# TPS5450.net
KiCad netlist of a schematic drawn in Altium Designer
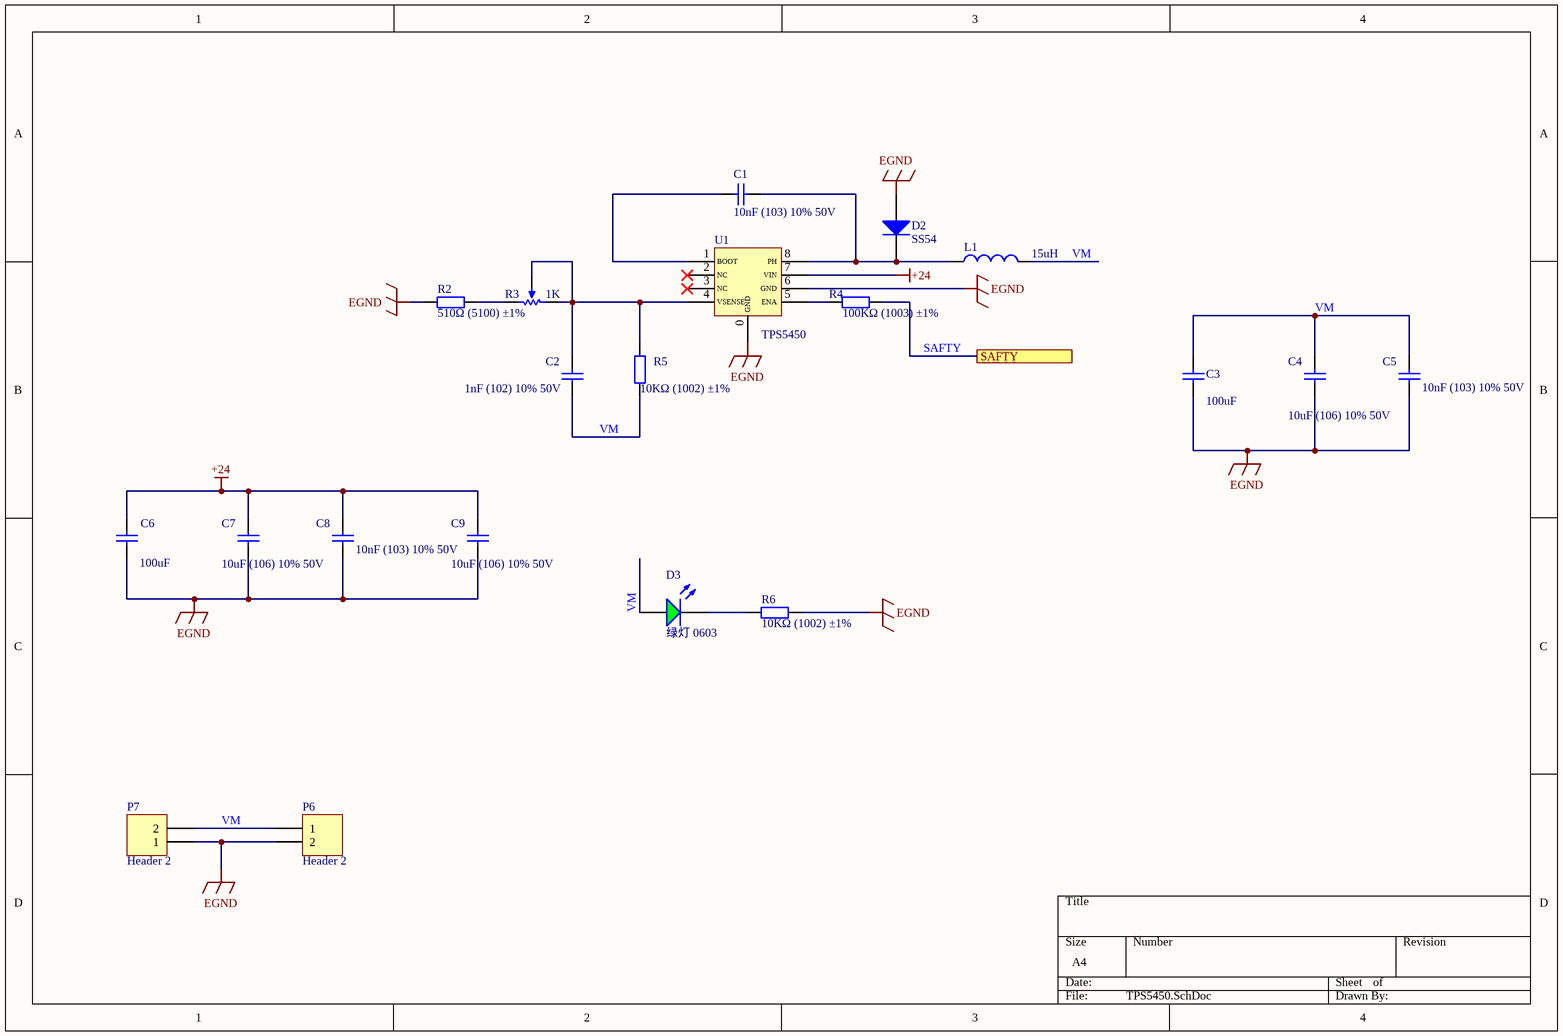
[diagram p0: TPS5450.SchDoc]

(export (version "E")
  (design (tool "Eeschema 10.0.6"))
  (components
    (comp (ref "C1")
      (value "10nF (103) 10% 50V")
      (footprint "0603_C")
      (description "贴片电容")
      (libsource (lib "Miscellaneous Devices LC") (part "0603 10nF (103) 10% 50V"))
    )
    (comp (ref "C2")
      (value "1nF (102) 10% 50V")
      (footprint "0603_C")
      (description "贴片电容")
      (libsource (lib "Miscellaneous Devices LC") (part "0603 1nF (102) 10% 50V"))
    )
    (comp (ref "C3")
      (value "100uF")
      (footprint "C100uF")
      (description "贴片电容")
      (fields (field (name "Comment") "Cap") (field (name "PUBLISHER") "Altium Limited"))
      (libsource (lib "Sparks") (part "Cap"))
    )
    (comp (ref "C4")
      (value "10uF (106) 10% 50V")
      (footprint "1206_C")
      (description "贴片电容")
      (libsource (lib "Miscellaneous Devices LC") (part "1206 10uF (106) 10% 50V"))
    )
    (comp (ref "C5")
      (value "10nF (103) 10% 50V")
      (footprint "0603_C")
      (description "贴片电容")
      (libsource (lib "Miscellaneous Devices LC") (part "0603 10nF (103) 10% 50V"))
    )
    (comp (ref "C6")
      (value "100uF")
      (footprint "C100uF")
      (description "贴片电容")
      (fields (field (name "Comment") "Cap") (field (name "PUBLISHER") "Altium Limited"))
      (libsource (lib "Sparks") (part "Cap"))
    )
    (comp (ref "C7")
      (value "10uF (106) 10% 50V")
      (footprint "1206_C")
      (description "贴片电容")
      (libsource (lib "Miscellaneous Devices LC") (part "1206 10uF (106) 10% 50V"))
    )
    (comp (ref "C8")
      (value "10nF (103) 10% 50V")
      (footprint "0603_C")
      (description "贴片电容")
      (libsource (lib "Miscellaneous Devices LC") (part "0603 10nF (103) 10% 50V"))
    )
    (comp (ref "C9")
      (value "10uF (106) 10% 50V")
      (footprint "1206_C")
      (description "贴片电容")
      (libsource (lib "Miscellaneous Devices LC") (part "1206 10uF (106) 10% 50V"))
    )
    (comp (ref "D2")
      (value "SS54")
      (footprint "SMA(DO-214AC)_S1")
      (description "二极管")
      (libsource (lib "Diode") (part "SMA(DO-214AC) SS54"))
    )
    (comp (ref "D3")
      (value "绿灯 0603")
      (footprint "0603_LED_S1")
      (description "发光二极管")
      (libsource (lib "Miscellaneous Devices LC") (part "0603 绿灯"))
    )
    (comp (ref "L1")
      (value "15uH")
      (footprint "INDP175172X70M")
      (description "Inductor")
      (fields (field (name "PUBLISHER") "Altium Limited"))
      (libsource (lib "Miscellaneous Devices") (part "Inductor"))
    )
    (comp (ref "P6")
      (value "Header 2")
      (footprint "5.08-2P")
      (description "Header, 2-Pin")
      (fields (field (name "PUBLISHER") "Altium Limited"))
      (libsource (lib "Sparks") (part "Header 2"))
    )
    (comp (ref "P7")
      (value "Header 2")
      (footprint "XH-2A")
      (description "Header, 2-Pin")
      (fields (field (name "PUBLISHER") "Altium Limited"))
      (libsource (lib "") (part "Header 2_1"))
    )
    (comp (ref "R2")
      (value "510Ω (5100) ±1%")
      (footprint "0603_R")
      (description "贴片电阻")
      (libsource (lib "Miscellaneous Devices LC") (part "0603 510Ω (5100) 1%"))
    )
    (comp (ref "R3")
      (value "1K")
      (footprint "RP1")
      (description "电位器")
      (fields (field (name "Comment") "RPot") (field (name "PUBLISHER") "Altium Limited"))
      (libsource (lib "Sparks") (part "RPot"))
    )
    (comp (ref "R4")
      (value "100KΩ (1003) ±1%")
      (footprint "0603_R")
      (description "贴片电阻")
      (libsource (lib "Miscellaneous Devices LC") (part "0603 100KΩ (1003) 1%"))
    )
    (comp (ref "R5")
      (value "10KΩ (1002) ±1%")
      (footprint "0603_R")
      (description "贴片电阻")
      (libsource (lib "") (part "0603 10KΩ (1002) 1%_1"))
    )
    (comp (ref "R6")
      (value "10KΩ (1002) ±1%")
      (footprint "0603_R")
      (description "贴片电阻")
      (libsource (lib "Miscellaneous Devices LC") (part "0603 10KΩ (1002) 1%"))
    )
    (comp (ref "U1")
      (value "TPS5450")
      (footprint "LC-SOP-8_EP_150mil")
      (libsource (lib "2号库") (part "TPS5450"))
    )
  )
  (nets
    (net (code "1") (name "+24") (class "Default")
      (node (ref "C6") (pin "2") (pinfunction "2_2") (pintype "passive"))
      (node (ref "C7") (pin "2") (pinfunction "2_2") (pintype "passive"))
      (node (ref "C8") (pin "2") (pinfunction "2_2") (pintype "passive"))
      (node (ref "C9") (pin "2") (pinfunction "2_2") (pintype "passive"))
      (node (ref "U1") (pin "7") (pinfunction "VIN_7") (pintype "passive"))
    )
    (net (code "2") (name "/SAFTY") (class "Default")
      (node (ref "R4") (pin "2") (pinfunction "2_2") (pintype "passive"))
    )
    (net (code "3") (name "/VM") (class "Default")
      (node (ref "C2") (pin "1") (pinfunction "1_1") (pintype "passive"))
      (node (ref "C3") (pin "2") (pinfunction "2_2") (pintype "passive"))
      (node (ref "C4") (pin "2") (pinfunction "2_2") (pintype "passive"))
      (node (ref "C5") (pin "2") (pinfunction "2_2") (pintype "passive"))
      (node (ref "D3") (pin "A") (pinfunction "A_A") (pintype "passive"))
      (node (ref "L1") (pin "2") (pinfunction "2_2") (pintype "passive"))
      (node (ref "P6") (pin "1") (pinfunction "1_1") (pintype "passive"))
      (node (ref "P7") (pin "2") (pinfunction "2_2") (pintype "passive"))
      (node (ref "R5") (pin "1") (pinfunction "1_1") (pintype "passive"))
    )
    (net (code "4") (name "EGND") (class "Default")
      (node (ref "C3") (pin "1") (pinfunction "1_1") (pintype "passive"))
      (node (ref "C4") (pin "1") (pinfunction "1_1") (pintype "passive"))
      (node (ref "C5") (pin "1") (pinfunction "1_1") (pintype "passive"))
      (node (ref "C6") (pin "1") (pinfunction "1_1") (pintype "passive"))
      (node (ref "C7") (pin "1") (pinfunction "1_1") (pintype "passive"))
      (node (ref "C8") (pin "1") (pinfunction "1_1") (pintype "passive"))
      (node (ref "C9") (pin "1") (pinfunction "1_1") (pintype "passive"))
      (node (ref "D2") (pin "1") (pinfunction "A_1") (pintype "passive"))
      (node (ref "P6") (pin "2") (pinfunction "2_2") (pintype "passive"))
      (node (ref "P7") (pin "1") (pinfunction "1_1") (pintype "passive"))
      (node (ref "R2") (pin "1") (pinfunction "1_1") (pintype "passive"))
      (node (ref "R6") (pin "2") (pinfunction "2_2") (pintype "passive"))
      (node (ref "U1") (pin "0") (pinfunction "GND_0") (pintype "passive"))
      (node (ref "U1") (pin "6") (pinfunction "GND_6") (pintype "passive"))
    )
    (net (code "5") (name "Net-(D2-K)") (class "Default")
      (node (ref "C1") (pin "2") (pinfunction "2_2") (pintype "passive"))
      (node (ref "D2") (pin "2") (pinfunction "K_2") (pintype "passive"))
      (node (ref "L1") (pin "1") (pinfunction "1_1") (pintype "passive"))
      (node (ref "U1") (pin "8") (pinfunction "PH_8") (pintype "passive"))
    )
    (net (code "6") (name "Net-(D3-PadK)") (class "Default")
      (node (ref "D3") (pin "K") (pinfunction "K_K") (pintype "passive"))
      (node (ref "R6") (pin "1") (pinfunction "1_1") (pintype "passive"))
    )
    (net (code "7") (name "Net-(R3-BOT)") (class "Default")
      (node (ref "C2") (pin "2") (pinfunction "2_2") (pintype "passive"))
      (node (ref "R3") (pin "2") (pinfunction "TAP_2") (pintype "passive"))
      (node (ref "R3") (pin "3") (pinfunction "BOT_3") (pintype "passive"))
      (node (ref "R5") (pin "2") (pinfunction "2_2") (pintype "passive"))
      (node (ref "U1") (pin "4") (pinfunction "VSENSE_4") (pintype "passive"))
    )
    (net (code "8") (name "Net-(R3-TOP)") (class "Default")
      (node (ref "R2") (pin "2") (pinfunction "2_2") (pintype "passive"))
      (node (ref "R3") (pin "1") (pinfunction "TOP_1") (pintype "passive"))
    )
    (net (code "9") (name "Net-(U1-BOOT)") (class "Default")
      (node (ref "C1") (pin "1") (pinfunction "1_1") (pintype "passive"))
      (node (ref "U1") (pin "1") (pinfunction "BOOT_1") (pintype "passive"))
    )
    (net (code "10") (name "Net-(U1-ENA)") (class "Default")
      (node (ref "R4") (pin "1") (pinfunction "1_1") (pintype "passive"))
      (node (ref "U1") (pin "5") (pinfunction "ENA_5") (pintype "passive"))
    )
    (net (code "11") (name "unconnected-(U1-NC-Pad2)") (class "Default")
      (node (ref "U1") (pin "2") (pinfunction "NC_2") (pintype "passive+no_connect"))
    )
    (net (code "12") (name "unconnected-(U1-NC-Pad3)") (class "Default")
      (node (ref "U1") (pin "3") (pinfunction "NC_3") (pintype "passive+no_connect"))
    )
  )
)
